# BSPD_rev11.net
KiCad netlist of a schematic drawn in EAGLE
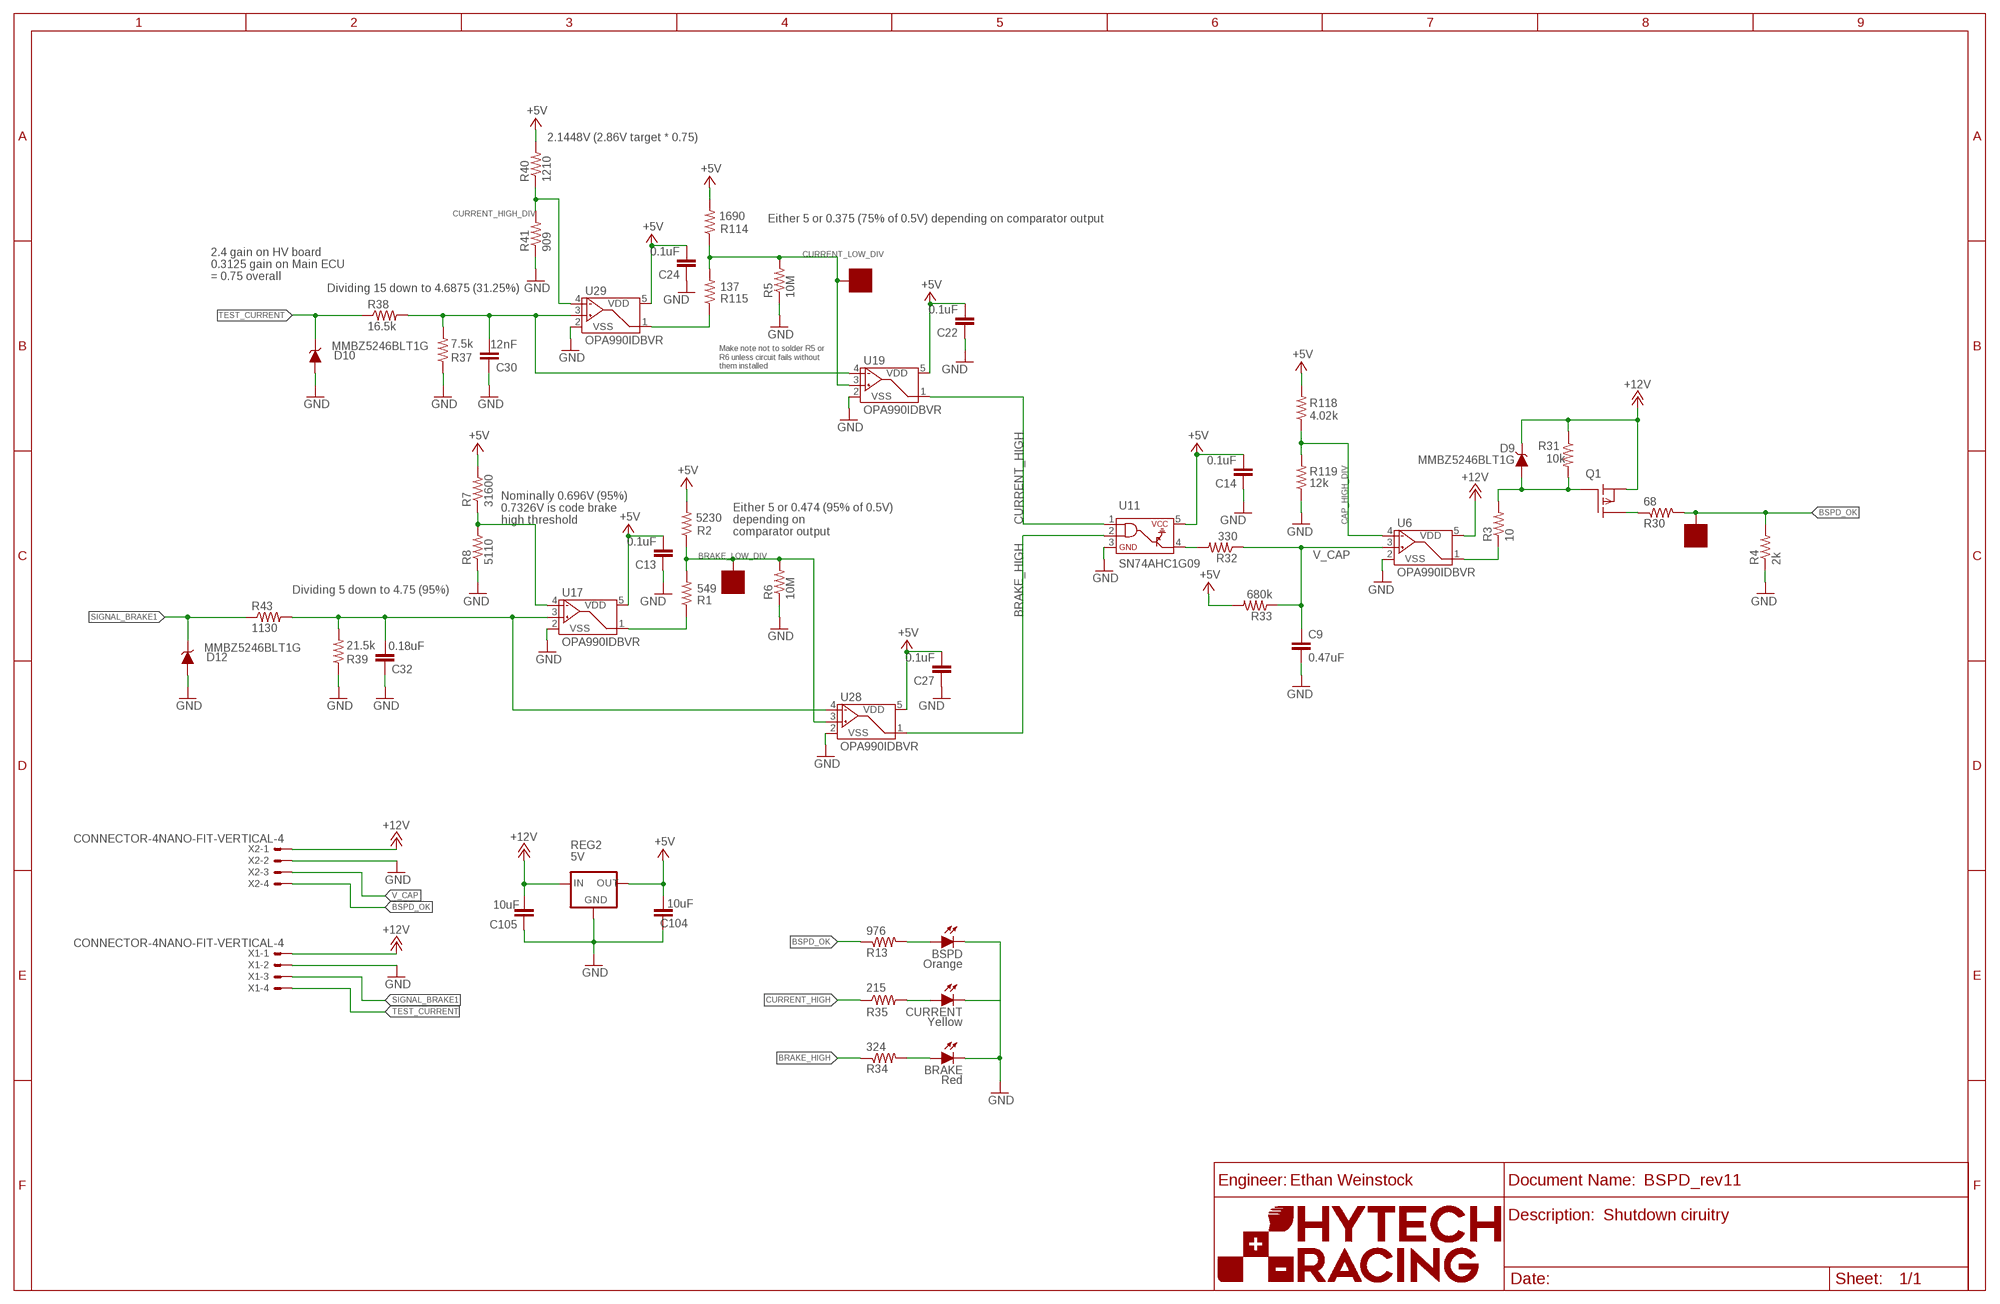
[diagram p0: schematic, sheet 1]

(export (version "E")
  (design (tool "Eeschema 10.0.6"))
  (components
    (comp (ref "BRAKE")
      (value "Red")
      (footprint "eagle-import:LED-805")
      (libsource (lib "eagle-import") (part "LED-0805"))
    )
    (comp (ref "BRAKE_LOW_DIV")
      (value "SOLDER_PAD")
      (footprint "eagle-import:SOLDER_PAD_XSMALL")
      (libsource (lib "eagle-import") (part "SOLDER_PAD"))
    )
    (comp (ref "BSPD")
      (value "Orange")
      (footprint "eagle-import:LED-805")
      (libsource (lib "eagle-import") (part "LED-0805"))
    )
    (comp (ref "BSPD_OK")
      (value "SOLDER_PAD")
      (footprint "eagle-import:SOLDER_PAD_XSMALL")
      (libsource (lib "eagle-import") (part "SOLDER_PAD"))
    )
    (comp (ref "C9")
      (value "0.47uF")
      (footprint "eagle-import:0603-CAP")
      (libsource (lib "eagle-import") (part "CAP0603-CAP"))
    )
    (comp (ref "C13")
      (value "0.1uF")
      (footprint "eagle-import:0603-CAP")
      (libsource (lib "eagle-import") (part "CAP0603-CAP"))
    )
    (comp (ref "C14")
      (value "0.1uF")
      (footprint "eagle-import:0603-CAP")
      (libsource (lib "eagle-import") (part "CAP0603-CAP"))
    )
    (comp (ref "C22")
      (value "0.1uF")
      (footprint "eagle-import:0603-CAP")
      (libsource (lib "eagle-import") (part "CAP0603-CAP"))
    )
    (comp (ref "C24")
      (value "0.1uF")
      (footprint "eagle-import:0603-CAP")
      (libsource (lib "eagle-import") (part "CAP0603-CAP"))
    )
    (comp (ref "C27")
      (value "0.1uF")
      (footprint "eagle-import:0603-CAP")
      (libsource (lib "eagle-import") (part "CAP0603-CAP"))
    )
    (comp (ref "C30")
      (value "12nF")
      (footprint "eagle-import:0603-CAP")
      (libsource (lib "eagle-import") (part "CAP0603-CAP"))
    )
    (comp (ref "C32")
      (value "0.18uF")
      (footprint "eagle-import:0603-CAP")
      (libsource (lib "eagle-import") (part "CAP0603-CAP"))
    )
    (comp (ref "C104")
      (value "10uF")
      (footprint "eagle-import:0603-CAP")
      (libsource (lib "eagle-import") (part "CAP0603-CAP"))
    )
    (comp (ref "C105")
      (value "10uF")
      (footprint "eagle-import:0603-CAP")
      (libsource (lib "eagle-import") (part "CAP0603-CAP"))
    )
    (comp (ref "CURRENT")
      (value "Yellow")
      (footprint "eagle-import:LED-805")
      (libsource (lib "eagle-import") (part "LED-0805"))
    )
    (comp (ref "CURRENT_LOW_DIV")
      (value "SOLDER_PAD")
      (footprint "eagle-import:SOLDER_PAD_XSMALL")
      (libsource (lib "eagle-import") (part "SOLDER_PAD"))
    )
    (comp (ref "D9")
      (value "MMBZ5246BLT1G")
      (footprint "eagle-import:SOT23")
      (libsource (lib "eagle-import") (part "DIODE_ZENER"))
    )
    (comp (ref "D10")
      (value "MMBZ5246BLT1G")
      (footprint "eagle-import:SOT23")
      (libsource (lib "eagle-import") (part "DIODE_ZENER"))
    )
    (comp (ref "D12")
      (value "MMBZ5246BLT1G")
      (footprint "eagle-import:SOT23")
      (libsource (lib "eagle-import") (part "DIODE_ZENER"))
    )
    (comp (ref "Q1")
      (value "P-CHANNEL_MOSFET_DMP3099L-7")
      (footprint "eagle-import:SOT23")
      (libsource (lib "eagle-import") (part "P-CHANNEL_MOSFET_DMP3099L-7"))
    )
    (comp (ref "R1")
      (value "549")
      (footprint "eagle-import:0603-RES")
      (libsource (lib "eagle-import") (part "RESISTOR0603"))
    )
    (comp (ref "R2")
      (value "5230")
      (footprint "eagle-import:0603-RES")
      (libsource (lib "eagle-import") (part "RESISTOR0603"))
    )
    (comp (ref "R3")
      (value "10")
      (footprint "eagle-import:0603-RES")
      (libsource (lib "eagle-import") (part "RESISTOR0603"))
    )
    (comp (ref "R4")
      (value "2k")
      (footprint "eagle-import:0603-RES")
      (libsource (lib "eagle-import") (part "RESISTOR0603"))
    )
    (comp (ref "R5")
      (value "10M")
      (footprint "eagle-import:0603-RES")
      (libsource (lib "eagle-import") (part "RESISTOR0603"))
    )
    (comp (ref "R6")
      (value "10M")
      (footprint "eagle-import:0603-RES")
      (libsource (lib "eagle-import") (part "RESISTOR0603"))
    )
    (comp (ref "R7")
      (value "31600")
      (footprint "eagle-import:0603-RES")
      (libsource (lib "eagle-import") (part "RESISTOR0603"))
    )
    (comp (ref "R8")
      (value "5110")
      (footprint "eagle-import:0603-RES")
      (libsource (lib "eagle-import") (part "RESISTOR0603"))
    )
    (comp (ref "R13")
      (value "976")
      (footprint "eagle-import:0603-RES")
      (libsource (lib "eagle-import") (part "RESISTOR0603"))
    )
    (comp (ref "R30")
      (value "68")
      (footprint "eagle-import:0603-RES")
      (libsource (lib "eagle-import") (part "RESISTOR0603"))
    )
    (comp (ref "R31")
      (value "10k")
      (footprint "eagle-import:0603-RES")
      (libsource (lib "eagle-import") (part "RESISTOR0603"))
    )
    (comp (ref "R32")
      (value "330")
      (footprint "eagle-import:0603-RES")
      (libsource (lib "eagle-import") (part "RESISTOR0603"))
    )
    (comp (ref "R33")
      (value "680k")
      (footprint "eagle-import:0603-RES")
      (libsource (lib "eagle-import") (part "RESISTOR0603"))
    )
    (comp (ref "R34")
      (value "324")
      (footprint "eagle-import:0603-RES")
      (libsource (lib "eagle-import") (part "RESISTOR0603"))
    )
    (comp (ref "R35")
      (value "215")
      (footprint "eagle-import:0603-RES")
      (libsource (lib "eagle-import") (part "RESISTOR0603"))
    )
    (comp (ref "R37")
      (value "7.5k")
      (footprint "eagle-import:0603-RES")
      (libsource (lib "eagle-import") (part "RESISTOR0603"))
    )
    (comp (ref "R38")
      (value "16.5k")
      (footprint "eagle-import:0603-RES")
      (libsource (lib "eagle-import") (part "RESISTOR0603"))
    )
    (comp (ref "R39")
      (value "21.5k")
      (footprint "eagle-import:0603-RES")
      (libsource (lib "eagle-import") (part "RESISTOR0603"))
    )
    (comp (ref "R40")
      (value "1210")
      (footprint "eagle-import:0603-RES")
      (libsource (lib "eagle-import") (part "RESISTOR0603"))
    )
    (comp (ref "R41")
      (value "909")
      (footprint "eagle-import:0603-RES")
      (libsource (lib "eagle-import") (part "RESISTOR0603"))
    )
    (comp (ref "R43")
      (value "1130")
      (footprint "eagle-import:0603-RES")
      (libsource (lib "eagle-import") (part "RESISTOR0603"))
    )
    (comp (ref "R114")
      (value "1690")
      (footprint "eagle-import:0603-RES")
      (libsource (lib "eagle-import") (part "RESISTOR0603"))
    )
    (comp (ref "R115")
      (value "137")
      (footprint "eagle-import:0603-RES")
      (libsource (lib "eagle-import") (part "RESISTOR0603"))
    )
    (comp (ref "R118")
      (value "4.02k")
      (footprint "eagle-import:0603-RES")
      (libsource (lib "eagle-import") (part "RESISTOR0603"))
    )
    (comp (ref "R119")
      (value "12k")
      (footprint "eagle-import:0603-RES")
      (libsource (lib "eagle-import") (part "RESISTOR0603"))
    )
    (comp (ref "REG2")
      (value "5V")
      (footprint "eagle-import:OKI-78SR")
      (libsource (lib "eagle-import") (part "OKI-78SR-5"))
    )
    (comp (ref "U6")
      (value "OPA990IDBVR")
      (footprint "eagle-import:SOT-23-5")
      (libsource (lib "eagle-import") (part "OPA990IDBVR"))
    )
    (comp (ref "U11")
      (value "SN74AHC1G09")
      (footprint "eagle-import:SOT-23-5")
      (libsource (lib "eagle-import") (part "SN74AHC1G09"))
    )
    (comp (ref "U17")
      (value "OPA990IDBVR")
      (footprint "eagle-import:SOT-23-5")
      (libsource (lib "eagle-import") (part "OPA990IDBVR"))
    )
    (comp (ref "U19")
      (value "OPA990IDBVR")
      (footprint "eagle-import:SOT-23-5")
      (libsource (lib "eagle-import") (part "OPA990IDBVR"))
    )
    (comp (ref "U28")
      (value "OPA990IDBVR")
      (footprint "eagle-import:SOT-23-5")
      (libsource (lib "eagle-import") (part "OPA990IDBVR"))
    )
    (comp (ref "U29")
      (value "OPA990IDBVR")
      (footprint "eagle-import:SOT-23-5")
      (libsource (lib "eagle-import") (part "OPA990IDBVR"))
    )
    (comp (ref "X1")
      (value "CONNECTOR-4NANO-FIT-VERTICAL-4")
      (footprint "eagle-import:NANO-FIT_VERTICAL-4")
      (libsource (lib "eagle-import") (part "CONNECTOR-4NANO-FIT-VERTICAL-4"))
    )
    (comp (ref "X2")
      (value "CONNECTOR-4NANO-FIT-VERTICAL-4")
      (footprint "eagle-import:NANO-FIT_VERTICAL-4")
      (libsource (lib "eagle-import") (part "CONNECTOR-4NANO-FIT-VERTICAL-4"))
    )
  )
  (nets
    (net (code "1") (name "+5V") (class "Default")
      (node (ref "C104") (pin "2") (pinfunction "2_2") (pintype "passive"))
      (node (ref "C13") (pin "2") (pinfunction "2_2") (pintype "passive"))
      (node (ref "C14") (pin "2") (pinfunction "2_2") (pintype "passive"))
      (node (ref "C22") (pin "2") (pinfunction "2_2") (pintype "passive"))
      (node (ref "C24") (pin "2") (pinfunction "2_2") (pintype "passive"))
      (node (ref "C27") (pin "2") (pinfunction "2_2") (pintype "passive"))
      (node (ref "R114") (pin "2") (pinfunction "2_2") (pintype "passive"))
      (node (ref "R118") (pin "2") (pinfunction "2_2") (pintype "passive"))
      (node (ref "R2") (pin "2") (pinfunction "2_2") (pintype "passive"))
      (node (ref "R33") (pin "2") (pinfunction "2_2") (pintype "passive"))
      (node (ref "R40") (pin "2") (pinfunction "2_2") (pintype "passive"))
      (node (ref "R7") (pin "2") (pinfunction "2_2") (pintype "passive"))
      (node (ref "REG2") (pin "3") (pinfunction "OUT_3") (pintype "passive"))
      (node (ref "U11") (pin "5") (pinfunction "5_5") (pintype "passive"))
      (node (ref "U17") (pin "5") (pinfunction "VDD_5") (pintype "passive"))
      (node (ref "U19") (pin "5") (pinfunction "VDD_5") (pintype "passive"))
      (node (ref "U28") (pin "5") (pinfunction "VDD_5") (pintype "passive"))
      (node (ref "U29") (pin "5") (pinfunction "VDD_5") (pintype "passive"))
    )
    (net (code "2") (name "+12V") (class "Default")
      (node (ref "C105") (pin "2") (pinfunction "2_2") (pintype "passive"))
      (node (ref "D9") (pin "3") (pinfunction "C_3") (pintype "passive"))
      (node (ref "Q1") (pin "2") (pinfunction "S_2") (pintype "passive"))
      (node (ref "R31") (pin "1") (pinfunction "1_1") (pintype "passive"))
      (node (ref "REG2") (pin "1") (pinfunction "IN_1") (pintype "input"))
      (node (ref "U6") (pin "5") (pinfunction "VDD_5") (pintype "passive"))
      (node (ref "X1") (pin "P$1") (pinfunction "S_P$1") (pintype "passive"))
      (node (ref "X2") (pin "P$1") (pinfunction "S_P$1") (pintype "passive"))
    )
    (net (code "3") (name "/BRAKE_LOW_DIV") (class "Default")
      (node (ref "BRAKE_LOW_DIV") (pin "P$1") (pinfunction "P$1_P$1") (pintype "bidirectional"))
      (node (ref "R1") (pin "2") (pinfunction "2_2") (pintype "passive"))
      (node (ref "R2") (pin "1") (pinfunction "1_1") (pintype "passive"))
      (node (ref "R6") (pin "2") (pinfunction "2_2") (pintype "passive"))
      (node (ref "U28") (pin "3") (pinfunction "VIN+_3") (pintype "passive"))
    )
    (net (code "4") (name "/CAP_HIGH_DIV") (class "Default")
      (node (ref "R118") (pin "1") (pinfunction "1_1") (pintype "passive"))
      (node (ref "R119") (pin "2") (pinfunction "2_2") (pintype "passive"))
      (node (ref "U6") (pin "4") (pinfunction "VIN-_4") (pintype "passive"))
    )
    (net (code "5") (name "/CURRENT_HIGH_DIV") (class "Default")
      (node (ref "R40") (pin "1") (pinfunction "1_1") (pintype "passive"))
      (node (ref "R41") (pin "2") (pinfunction "2_2") (pintype "passive"))
      (node (ref "U29") (pin "4") (pinfunction "VIN-_4") (pintype "passive"))
    )
    (net (code "6") (name "/CURRENT_LOW_DIV") (class "Default")
      (node (ref "CURRENT_LOW_DIV") (pin "P$1") (pinfunction "P$1_P$1") (pintype "bidirectional"))
      (node (ref "R114") (pin "1") (pinfunction "1_1") (pintype "passive"))
      (node (ref "R115") (pin "2") (pinfunction "2_2") (pintype "passive"))
      (node (ref "R5") (pin "2") (pinfunction "2_2") (pintype "passive"))
      (node (ref "U19") (pin "3") (pinfunction "VIN+_3") (pintype "passive"))
    )
    (net (code "7") (name "BRAKE_HIGH") (class "Default")
      (node (ref "R34") (pin "1") (pinfunction "1_1") (pintype "passive"))
      (node (ref "U11") (pin "2") (pinfunction "2_2") (pintype "passive"))
      (node (ref "U28") (pin "1") (pinfunction "VOUT_1") (pintype "passive"))
    )
    (net (code "8") (name "BSPD_OK") (class "Default")
      (node (ref "BSPD_OK") (pin "P$1") (pinfunction "P$1_P$1") (pintype "bidirectional"))
      (node (ref "R13") (pin "1") (pinfunction "1_1") (pintype "passive"))
      (node (ref "R30") (pin "2") (pinfunction "2_2") (pintype "passive"))
      (node (ref "R4") (pin "2") (pinfunction "2_2") (pintype "passive"))
      (node (ref "X2") (pin "P$4") (pinfunction "S_P$4") (pintype "passive"))
    )
    (net (code "9") (name "CURRENT_HIGH") (class "Default")
      (node (ref "R35") (pin "1") (pinfunction "1_1") (pintype "passive"))
      (node (ref "U11") (pin "1") (pinfunction "1_1") (pintype "passive"))
      (node (ref "U19") (pin "1") (pinfunction "VOUT_1") (pintype "passive"))
    )
    (net (code "10") (name "GND") (class "Default")
      (node (ref "BRAKE") (pin "C") (pinfunction "C_C") (pintype "passive"))
      (node (ref "BSPD") (pin "C") (pinfunction "C_C") (pintype "passive"))
      (node (ref "C104") (pin "1") (pinfunction "1_1") (pintype "passive"))
      (node (ref "C105") (pin "1") (pinfunction "1_1") (pintype "passive"))
      (node (ref "C13") (pin "1") (pinfunction "1_1") (pintype "passive"))
      (node (ref "C14") (pin "1") (pinfunction "1_1") (pintype "passive"))
      (node (ref "C22") (pin "1") (pinfunction "1_1") (pintype "passive"))
      (node (ref "C24") (pin "1") (pinfunction "1_1") (pintype "passive"))
      (node (ref "C27") (pin "1") (pinfunction "1_1") (pintype "passive"))
      (node (ref "C30") (pin "1") (pinfunction "1_1") (pintype "passive"))
      (node (ref "C32") (pin "1") (pinfunction "1_1") (pintype "passive"))
      (node (ref "C9") (pin "2") (pinfunction "2_2") (pintype "passive"))
      (node (ref "CURRENT") (pin "C") (pinfunction "C_C") (pintype "passive"))
      (node (ref "D10") (pin "1") (pinfunction "A_1") (pintype "passive"))
      (node (ref "D12") (pin "1") (pinfunction "A_1") (pintype "passive"))
      (node (ref "R119") (pin "1") (pinfunction "1_1") (pintype "passive"))
      (node (ref "R37") (pin "1") (pinfunction "1_1") (pintype "passive"))
      (node (ref "R39") (pin "1") (pinfunction "1_1") (pintype "passive"))
      (node (ref "R4") (pin "1") (pinfunction "1_1") (pintype "passive"))
      (node (ref "R41") (pin "1") (pinfunction "1_1") (pintype "passive"))
      (node (ref "R5") (pin "1") (pinfunction "1_1") (pintype "passive"))
      (node (ref "R6") (pin "1") (pinfunction "1_1") (pintype "passive"))
      (node (ref "R8") (pin "1") (pinfunction "1_1") (pintype "passive"))
      (node (ref "REG2") (pin "2") (pinfunction "GND_2") (pintype "input"))
      (node (ref "U11") (pin "3") (pinfunction "3_3") (pintype "passive"))
      (node (ref "U17") (pin "2") (pinfunction "VSS_2") (pintype "passive"))
      (node (ref "U19") (pin "2") (pinfunction "VSS_2") (pintype "passive"))
      (node (ref "U28") (pin "2") (pinfunction "VSS_2") (pintype "passive"))
      (node (ref "U29") (pin "2") (pinfunction "VSS_2") (pintype "passive"))
      (node (ref "U6") (pin "2") (pinfunction "VSS_2") (pintype "passive"))
      (node (ref "X1") (pin "P$2") (pinfunction "S_P$2") (pintype "passive"))
      (node (ref "X2") (pin "P$2") (pinfunction "S_P$2") (pintype "passive"))
    )
    (net (code "11") (name "Net-(BRAKE-PadA)") (class "Default")
      (node (ref "BRAKE") (pin "A") (pinfunction "A_A") (pintype "passive"))
      (node (ref "R34") (pin "2") (pinfunction "2_2") (pintype "passive"))
    )
    (net (code "12") (name "Net-(BSPD-PadA)") (class "Default")
      (node (ref "BSPD") (pin "A") (pinfunction "A_A") (pintype "passive"))
      (node (ref "R13") (pin "2") (pinfunction "2_2") (pintype "passive"))
    )
    (net (code "13") (name "Net-(CURRENT-PadA)") (class "Default")
      (node (ref "CURRENT") (pin "A") (pinfunction "A_A") (pintype "passive"))
      (node (ref "R35") (pin "2") (pinfunction "2_2") (pintype "passive"))
    )
    (net (code "14") (name "Net-(D9-A)") (class "Default")
      (node (ref "D9") (pin "1") (pinfunction "A_1") (pintype "passive"))
      (node (ref "Q1") (pin "1") (pinfunction "G_1") (pintype "passive"))
      (node (ref "R3") (pin "2") (pinfunction "2_2") (pintype "passive"))
      (node (ref "R31") (pin "2") (pinfunction "2_2") (pintype "passive"))
    )
    (net (code "15") (name "Net-(Q1-D)") (class "Default")
      (node (ref "Q1") (pin "3") (pinfunction "D_3") (pintype "passive"))
      (node (ref "R30") (pin "1") (pinfunction "1_1") (pintype "passive"))
    )
    (net (code "16") (name "Net-(R32-Pad2)") (class "Default")
      (node (ref "R32") (pin "2") (pinfunction "2_2") (pintype "passive"))
      (node (ref "U11") (pin "4") (pinfunction "4_4") (pintype "passive"))
    )
    (net (code "17") (name "Net-(U6-VOUT)") (class "Default")
      (node (ref "R3") (pin "1") (pinfunction "1_1") (pintype "passive"))
      (node (ref "U6") (pin "1") (pinfunction "VOUT_1") (pintype "passive"))
    )
    (net (code "18") (name "Net-(U17-VIN+)") (class "Default")
      (node (ref "C32") (pin "2") (pinfunction "2_2") (pintype "passive"))
      (node (ref "R39") (pin "2") (pinfunction "2_2") (pintype "passive"))
      (node (ref "R43") (pin "2") (pinfunction "2_2") (pintype "passive"))
      (node (ref "U17") (pin "3") (pinfunction "VIN+_3") (pintype "passive"))
      (node (ref "U28") (pin "4") (pinfunction "VIN-_4") (pintype "passive"))
    )
    (net (code "19") (name "Net-(U17-VIN-)") (class "Default")
      (node (ref "R7") (pin "1") (pinfunction "1_1") (pintype "passive"))
      (node (ref "R8") (pin "2") (pinfunction "2_2") (pintype "passive"))
      (node (ref "U17") (pin "4") (pinfunction "VIN-_4") (pintype "passive"))
    )
    (net (code "20") (name "Net-(U17-VOUT)") (class "Default")
      (node (ref "R1") (pin "1") (pinfunction "1_1") (pintype "passive"))
      (node (ref "U17") (pin "1") (pinfunction "VOUT_1") (pintype "passive"))
    )
    (net (code "21") (name "Net-(U19-VIN-)") (class "Default")
      (node (ref "C30") (pin "2") (pinfunction "2_2") (pintype "passive"))
      (node (ref "R37") (pin "2") (pinfunction "2_2") (pintype "passive"))
      (node (ref "R38") (pin "2") (pinfunction "2_2") (pintype "passive"))
      (node (ref "U19") (pin "4") (pinfunction "VIN-_4") (pintype "passive"))
      (node (ref "U29") (pin "3") (pinfunction "VIN+_3") (pintype "passive"))
    )
    (net (code "22") (name "Net-(U29-VOUT)") (class "Default")
      (node (ref "R115") (pin "1") (pinfunction "1_1") (pintype "passive"))
      (node (ref "U29") (pin "1") (pinfunction "VOUT_1") (pintype "passive"))
    )
    (net (code "23") (name "SIGNAL_BRAKE1") (class "Default")
      (node (ref "D12") (pin "3") (pinfunction "C_3") (pintype "passive"))
      (node (ref "R43") (pin "1") (pinfunction "1_1") (pintype "passive"))
      (node (ref "X1") (pin "P$3") (pinfunction "S_P$3") (pintype "passive"))
    )
    (net (code "24") (name "TEST_CURRENT") (class "Default")
      (node (ref "D10") (pin "3") (pinfunction "C_3") (pintype "passive"))
      (node (ref "R38") (pin "1") (pinfunction "1_1") (pintype "passive"))
      (node (ref "X1") (pin "P$4") (pinfunction "S_P$4") (pintype "passive"))
    )
    (net (code "25") (name "V_CAP") (class "Default")
      (node (ref "C9") (pin "1") (pinfunction "1_1") (pintype "passive"))
      (node (ref "R32") (pin "1") (pinfunction "1_1") (pintype "passive"))
      (node (ref "R33") (pin "1") (pinfunction "1_1") (pintype "passive"))
      (node (ref "U6") (pin "3") (pinfunction "VIN+_3") (pintype "passive"))
      (node (ref "X2") (pin "P$3") (pinfunction "S_P$3") (pintype "passive"))
    )
  )
)
